# PowerBoard-v1_1.net
KiCad netlist of a schematic drawn in EAGLE
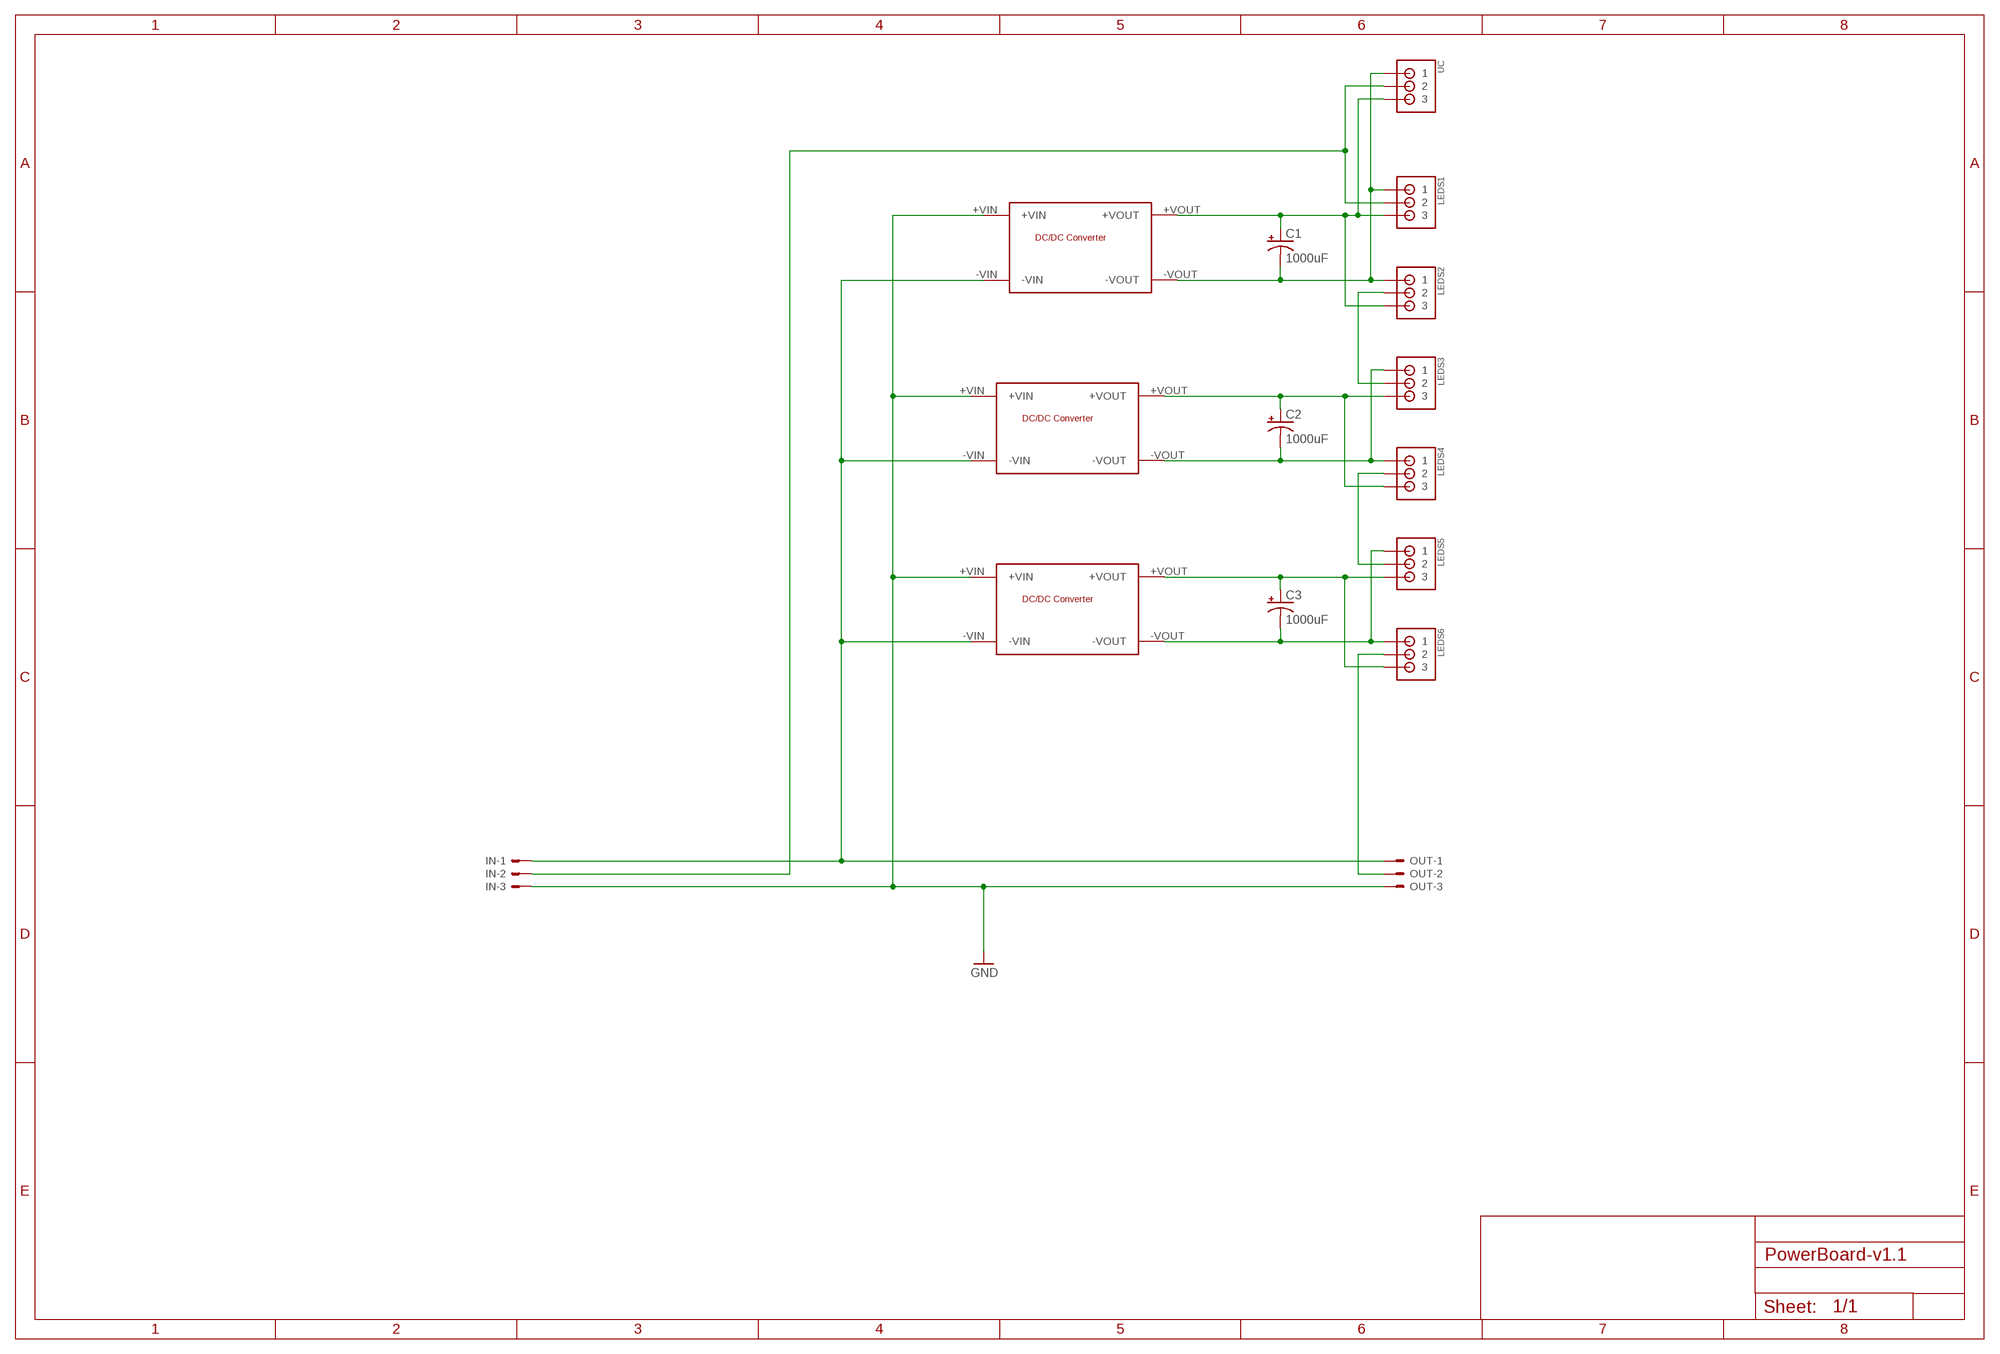
[diagram p0: schematic, sheet 1]

(export (version "E")
  (design (tool "Eeschema 10.0.6"))
  (components
    (comp (ref "C1")
      (value "1000uF")
      (footprint "eagle-import:CPOL-RADIAL-1000UF-25V")
      (libsource (lib "eagle-import") (part "CAP_POLPTH4"))
    )
    (comp (ref "C2")
      (value "1000uF")
      (footprint "eagle-import:CPOL-RADIAL-1000UF-25V")
      (libsource (lib "eagle-import") (part "CAP_POLPTH4"))
    )
    (comp (ref "C3")
      (value "1000uF")
      (footprint "eagle-import:CPOL-RADIAL-1000UF-25V")
      (libsource (lib "eagle-import") (part "CAP_POLPTH4"))
    )
    (comp (ref "IN")
      (value "22-23-2031")
      (footprint "eagle-import:22-23-2031")
      (fields (field (name "MF") "MOLEX"))
      (libsource (lib "eagle-import") (part "22-23-2031"))
    )
    (comp (ref "LEDS1")
      (value "JST-XA-03-PIN")
      (footprint "eagle-import:JST-XA-03")
      (libsource (lib "eagle-import") (part "JST-XA-03-PIN"))
    )
    (comp (ref "LEDS2")
      (value "JST-XA-03-PIN")
      (footprint "eagle-import:JST-XA-03")
      (libsource (lib "eagle-import") (part "JST-XA-03-PIN"))
    )
    (comp (ref "LEDS3")
      (value "JST-XA-03-PIN")
      (footprint "eagle-import:JST-XA-03")
      (libsource (lib "eagle-import") (part "JST-XA-03-PIN"))
    )
    (comp (ref "LEDS4")
      (value "JST-XA-03-PIN")
      (footprint "eagle-import:JST-XA-03")
      (libsource (lib "eagle-import") (part "JST-XA-03-PIN"))
    )
    (comp (ref "LEDS5")
      (value "JST-XA-03-PIN")
      (footprint "eagle-import:JST-XA-03")
      (libsource (lib "eagle-import") (part "JST-XA-03-PIN"))
    )
    (comp (ref "LEDS6")
      (value "JST-XA-03-PIN")
      (footprint "eagle-import:JST-XA-03")
      (libsource (lib "eagle-import") (part "JST-XA-03-PIN"))
    )
    (comp (ref "OUT")
      (value "22-23-2031")
      (footprint "eagle-import:22-23-2031")
      (fields (field (name "MF") "MOLEX"))
      (libsource (lib "eagle-import") (part "22-23-2031"))
    )
    (comp (ref "U$1")
      (value "DC-DC-CONVERTER")
      (footprint "eagle-import:MP1584EN-BUCK-CONVERTER")
      (libsource (lib "eagle-import") (part "DC-DC-CONVERTER"))
    )
    (comp (ref "U$2")
      (value "DC-DC-CONVERTER")
      (footprint "eagle-import:MP1584EN-BUCK-CONVERTER")
      (libsource (lib "eagle-import") (part "DC-DC-CONVERTER"))
    )
    (comp (ref "U$3")
      (value "DC-DC-CONVERTER")
      (footprint "eagle-import:MP1584EN-BUCK-CONVERTER")
      (libsource (lib "eagle-import") (part "DC-DC-CONVERTER"))
    )
    (comp (ref "UC")
      (value "JST-XA-03-PIN")
      (footprint "eagle-import:JST-XA-03")
      (libsource (lib "eagle-import") (part "JST-XA-03-PIN"))
    )
  )
  (nets
    (net (code "1") (name "GND") (class "Default")
      (node (ref "IN") (pin "3") (pinfunction "S_3") (pintype "passive"))
      (node (ref "OUT") (pin "3") (pinfunction "S_3") (pintype "passive"))
      (node (ref "U$1") (pin "+VIN") (pinfunction "+VIN_+VIN") (pintype "bidirectional"))
      (node (ref "U$2") (pin "+VIN") (pinfunction "+VIN_+VIN") (pintype "bidirectional"))
      (node (ref "U$3") (pin "+VIN") (pinfunction "+VIN_+VIN") (pintype "bidirectional"))
    )
    (net (code "2") (name "Net-(C1-Pad+)") (class "Default")
      (node (ref "C1") (pin "+") (pinfunction "+_+") (pintype "passive"))
      (node (ref "LEDS1") (pin "3") (pinfunction "3_3") (pintype "bidirectional"))
      (node (ref "LEDS2") (pin "3") (pinfunction "3_3") (pintype "bidirectional"))
      (node (ref "U$1") (pin "+VOUT") (pinfunction "+VOUT_+VOUT") (pintype "bidirectional"))
      (node (ref "UC") (pin "3") (pinfunction "3_3") (pintype "bidirectional"))
    )
    (net (code "3") (name "Net-(C1-Pad-)") (class "Default")
      (node (ref "C1") (pin "-") (pinfunction "-_-") (pintype "passive"))
      (node (ref "LEDS1") (pin "1") (pinfunction "1_1") (pintype "bidirectional"))
      (node (ref "LEDS2") (pin "1") (pinfunction "1_1") (pintype "bidirectional"))
      (node (ref "U$1") (pin "-VOUT") (pinfunction "-VOUT_-VOUT") (pintype "bidirectional"))
      (node (ref "UC") (pin "1") (pinfunction "1_1") (pintype "bidirectional"))
    )
    (net (code "4") (name "Net-(C2-Pad+)") (class "Default")
      (node (ref "C2") (pin "+") (pinfunction "+_+") (pintype "passive"))
      (node (ref "LEDS3") (pin "3") (pinfunction "3_3") (pintype "bidirectional"))
      (node (ref "LEDS4") (pin "3") (pinfunction "3_3") (pintype "bidirectional"))
      (node (ref "U$2") (pin "+VOUT") (pinfunction "+VOUT_+VOUT") (pintype "bidirectional"))
    )
    (net (code "5") (name "Net-(C2-Pad-)") (class "Default")
      (node (ref "C2") (pin "-") (pinfunction "-_-") (pintype "passive"))
      (node (ref "LEDS3") (pin "1") (pinfunction "1_1") (pintype "bidirectional"))
      (node (ref "LEDS4") (pin "1") (pinfunction "1_1") (pintype "bidirectional"))
      (node (ref "U$2") (pin "-VOUT") (pinfunction "-VOUT_-VOUT") (pintype "bidirectional"))
    )
    (net (code "6") (name "Net-(C3-Pad+)") (class "Default")
      (node (ref "C3") (pin "+") (pinfunction "+_+") (pintype "passive"))
      (node (ref "LEDS5") (pin "3") (pinfunction "3_3") (pintype "bidirectional"))
      (node (ref "LEDS6") (pin "3") (pinfunction "3_3") (pintype "bidirectional"))
      (node (ref "U$3") (pin "+VOUT") (pinfunction "+VOUT_+VOUT") (pintype "bidirectional"))
    )
    (net (code "7") (name "Net-(C3-Pad-)") (class "Default")
      (node (ref "C3") (pin "-") (pinfunction "-_-") (pintype "passive"))
      (node (ref "LEDS5") (pin "1") (pinfunction "1_1") (pintype "bidirectional"))
      (node (ref "LEDS6") (pin "1") (pinfunction "1_1") (pintype "bidirectional"))
      (node (ref "U$3") (pin "-VOUT") (pinfunction "-VOUT_-VOUT") (pintype "bidirectional"))
    )
    (net (code "8") (name "Net-(INA-S)") (class "Default")
      (node (ref "IN") (pin "1") (pinfunction "S_1") (pintype "passive"))
      (node (ref "OUT") (pin "1") (pinfunction "S_1") (pintype "passive"))
      (node (ref "U$1") (pin "-VIN") (pinfunction "-VIN_-VIN") (pintype "bidirectional"))
      (node (ref "U$2") (pin "-VIN") (pinfunction "-VIN_-VIN") (pintype "bidirectional"))
      (node (ref "U$3") (pin "-VIN") (pinfunction "-VIN_-VIN") (pintype "bidirectional"))
    )
    (net (code "9") (name "Net-(INB-S)") (class "Default")
      (node (ref "IN") (pin "2") (pinfunction "S_2") (pintype "passive"))
      (node (ref "LEDS1") (pin "2") (pinfunction "2_2") (pintype "bidirectional"))
      (node (ref "UC") (pin "2") (pinfunction "2_2") (pintype "bidirectional"))
    )
    (net (code "10") (name "Net-(LEDS2-Pad2)") (class "Default")
      (node (ref "LEDS2") (pin "2") (pinfunction "2_2") (pintype "bidirectional"))
      (node (ref "LEDS3") (pin "2") (pinfunction "2_2") (pintype "bidirectional"))
    )
    (net (code "11") (name "Net-(LEDS4-Pad2)") (class "Default")
      (node (ref "LEDS4") (pin "2") (pinfunction "2_2") (pintype "bidirectional"))
      (node (ref "LEDS5") (pin "2") (pinfunction "2_2") (pintype "bidirectional"))
    )
    (net (code "12") (name "Net-(OUTB-S)") (class "Default")
      (node (ref "LEDS6") (pin "2") (pinfunction "2_2") (pintype "bidirectional"))
      (node (ref "OUT") (pin "2") (pinfunction "S_2") (pintype "passive"))
    )
  )
)
